# boron-programmer.net
KiCad netlist of a schematic drawn in EAGLE
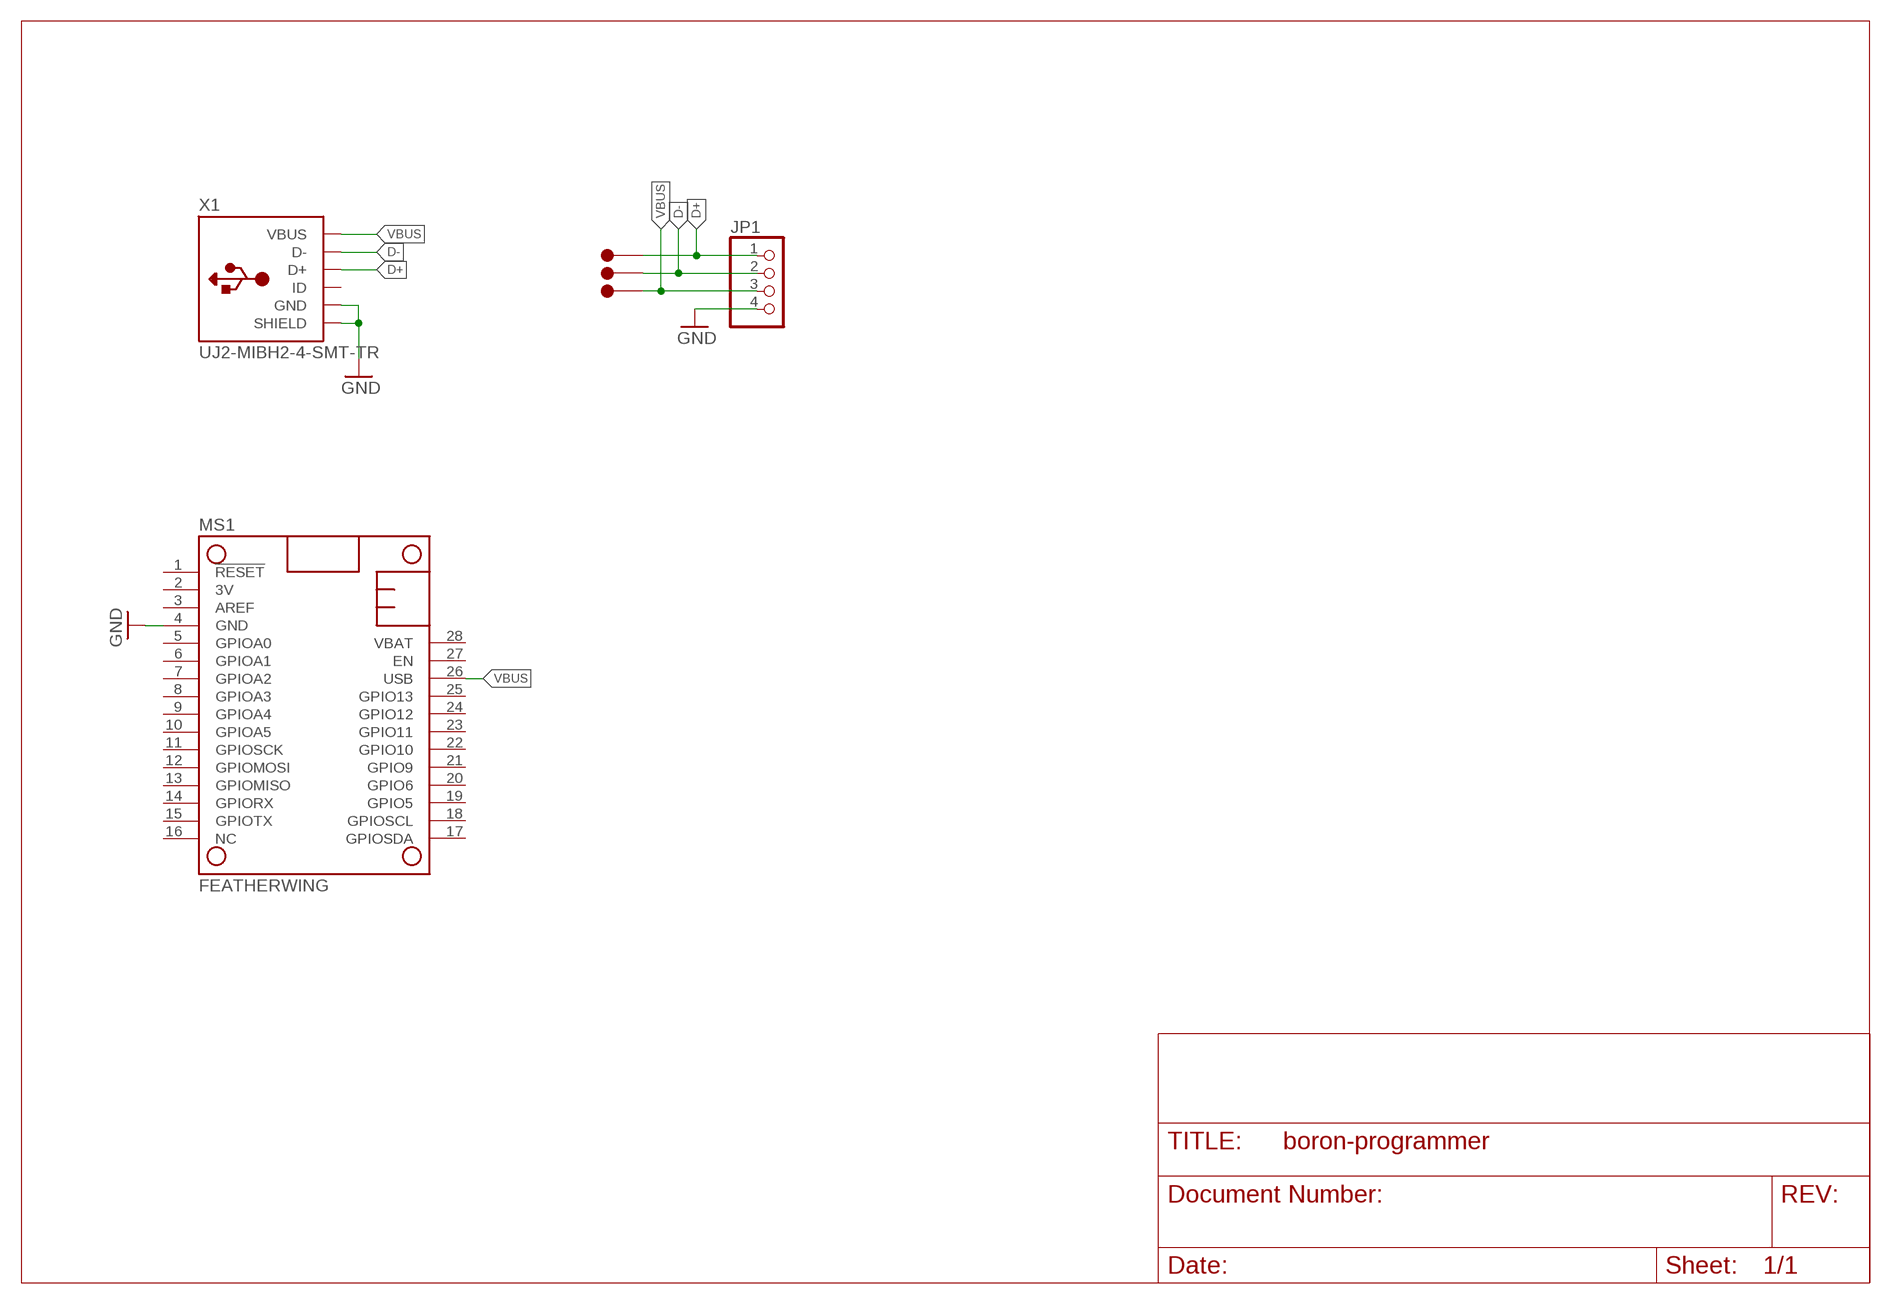
[diagram p0: schematic, sheet 1]

(export (version "E")
  (design (tool "Eeschema 10.0.6"))
  (components
    (comp (ref "C1")
      (value "POGO_PIN_1MM")
      (footprint "eagle-import:POGO_1MM")
      (libsource (lib "eagle-import") (part "POGO_PIN_1MM"))
    )
    (comp (ref "C2")
      (value "POGO_PIN_1MM")
      (footprint "eagle-import:POGO_1MM")
      (libsource (lib "eagle-import") (part "POGO_PIN_1MM"))
    )
    (comp (ref "C4")
      (value "POGO_PIN_1MM")
      (footprint "eagle-import:POGO_1MM")
      (libsource (lib "eagle-import") (part "POGO_PIN_1MM"))
    )
    (comp (ref "JP1")
      (value "PINHD-1X4")
      (footprint "eagle-import:1X04")
      (libsource (lib "eagle-import") (part "PINHD-1X4"))
    )
    (comp (ref "MS1")
      (value "FEATHERWING")
      (footprint "eagle-import:FEATHERWING")
      (libsource (lib "eagle-import") (part "FEATHERWING"))
    )
    (comp (ref "X1")
      (value "UJ2-MIBH2-4-SMT-TR")
      (footprint "eagle-import:MICRO_USB_B")
      (libsource (lib "eagle-import") (part "MICRO_USB_B"))
    )
  )
  (nets
    (net (code "1") (name "/3V") (class "Default")
      (node (ref "MS1") (pin "2") (pinfunction "3V_2") (pintype "power_in"))
    )
    (net (code "2") (name "/VBAT") (class "Default")
      (node (ref "MS1") (pin "28") (pinfunction "VBAT_28") (pintype "power_in"))
    )
    (net (code "3") (name "D+") (class "Default")
      (node (ref "C1") (pin "P$1") (pinfunction "P$1_P$1") (pintype "passive"))
      (node (ref "JP1") (pin "1") (pinfunction "1_1") (pintype "passive"))
      (node (ref "X1") (pin "D+") (pinfunction "D+_D+") (pintype "bidirectional"))
    )
    (net (code "4") (name "D-") (class "Default")
      (node (ref "C2") (pin "P$1") (pinfunction "P$1_P$1") (pintype "passive"))
      (node (ref "JP1") (pin "2") (pinfunction "2_2") (pintype "passive"))
      (node (ref "X1") (pin "D-") (pinfunction "D-_D-") (pintype "bidirectional"))
    )
    (net (code "5") (name "GND") (class "Default")
      (node (ref "JP1") (pin "4") (pinfunction "4_4") (pintype "passive"))
      (node (ref "MS1") (pin "4") (pinfunction "GND_4") (pintype "power_in"))
      (node (ref "X1") (pin "GND") (pinfunction "GND_GND") (pintype "power_in"))
      (node (ref "X1") (pin "SHIELD1") (pinfunction "SHIELD_SHIELD1") (pintype "passive"))
      (node (ref "X1") (pin "SHIELD2") (pinfunction "SHIELD_SHIELD2") (pintype "passive"))
      (node (ref "X1") (pin "SHIELD3") (pinfunction "SHIELD_SHIELD3") (pintype "passive"))
      (node (ref "X1") (pin "SHIELD4") (pinfunction "SHIELD_SHIELD4") (pintype "passive"))
      (node (ref "X1") (pin "SHIELD5") (pinfunction "SHIELD_SHIELD5") (pintype "passive"))
    )
    (net (code "6") (name "VBUS") (class "Default")
      (node (ref "C4") (pin "P$1") (pinfunction "P$1_P$1") (pintype "passive"))
      (node (ref "JP1") (pin "3") (pinfunction "3_3") (pintype "passive"))
      (node (ref "MS1") (pin "26") (pinfunction "USB_26") (pintype "power_in"))
      (node (ref "X1") (pin "VBUS") (pinfunction "VBUS_VBUS") (pintype "power_in"))
    )
    (net (code "7") (name "unconnected-(MS1-AREF-Pad3)") (class "Default")
      (node (ref "MS1") (pin "3") (pinfunction "AREF_3") (pintype "passive"))
    )
    (net (code "8") (name "unconnected-(MS1-EN-Pad27)") (class "Default")
      (node (ref "MS1") (pin "27") (pinfunction "EN_27") (pintype "passive"))
    )
    (net (code "9") (name "unconnected-(MS1-GPIO5-Pad19)") (class "Default")
      (node (ref "MS1") (pin "19") (pinfunction "GPIO5_19") (pintype "bidirectional"))
    )
    (net (code "10") (name "unconnected-(MS1-GPIO6-Pad20)") (class "Default")
      (node (ref "MS1") (pin "20") (pinfunction "GPIO6_20") (pintype "bidirectional"))
    )
    (net (code "11") (name "unconnected-(MS1-GPIO9-Pad21)") (class "Default")
      (node (ref "MS1") (pin "21") (pinfunction "GPIO9_21") (pintype "bidirectional"))
    )
    (net (code "12") (name "unconnected-(MS1-GPIO10-Pad22)") (class "Default")
      (node (ref "MS1") (pin "22") (pinfunction "GPIO10_22") (pintype "bidirectional"))
    )
    (net (code "13") (name "unconnected-(MS1-GPIO11-Pad23)") (class "Default")
      (node (ref "MS1") (pin "23") (pinfunction "GPIO11_23") (pintype "bidirectional"))
    )
    (net (code "14") (name "unconnected-(MS1-GPIO12-Pad24)") (class "Default")
      (node (ref "MS1") (pin "24") (pinfunction "GPIO12_24") (pintype "bidirectional"))
    )
    (net (code "15") (name "unconnected-(MS1-GPIO13-Pad25)") (class "Default")
      (node (ref "MS1") (pin "25") (pinfunction "GPIO13_25") (pintype "bidirectional"))
    )
    (net (code "16") (name "unconnected-(MS1-GPIOA0-Pad5)") (class "Default")
      (node (ref "MS1") (pin "5") (pinfunction "GPIOA0_5") (pintype "bidirectional"))
    )
    (net (code "17") (name "unconnected-(MS1-GPIOA1-Pad6)") (class "Default")
      (node (ref "MS1") (pin "6") (pinfunction "GPIOA1_6") (pintype "bidirectional"))
    )
    (net (code "18") (name "unconnected-(MS1-GPIOA2-Pad7)") (class "Default")
      (node (ref "MS1") (pin "7") (pinfunction "GPIOA2_7") (pintype "bidirectional"))
    )
    (net (code "19") (name "unconnected-(MS1-GPIOA3-Pad8)") (class "Default")
      (node (ref "MS1") (pin "8") (pinfunction "GPIOA3_8") (pintype "bidirectional"))
    )
    (net (code "20") (name "unconnected-(MS1-GPIOA4-Pad9)") (class "Default")
      (node (ref "MS1") (pin "9") (pinfunction "GPIOA4_9") (pintype "bidirectional"))
    )
    (net (code "21") (name "unconnected-(MS1-GPIOA5-Pad10)") (class "Default")
      (node (ref "MS1") (pin "10") (pinfunction "GPIOA5_10") (pintype "bidirectional"))
    )
    (net (code "22") (name "unconnected-(MS1-GPIOMISO-Pad13)") (class "Default")
      (node (ref "MS1") (pin "13") (pinfunction "GPIOMISO_13") (pintype "bidirectional"))
    )
    (net (code "23") (name "unconnected-(MS1-GPIOMOSI-Pad12)") (class "Default")
      (node (ref "MS1") (pin "12") (pinfunction "GPIOMOSI_12") (pintype "bidirectional"))
    )
    (net (code "24") (name "unconnected-(MS1-GPIORX-Pad14)") (class "Default")
      (node (ref "MS1") (pin "14") (pinfunction "GPIORX_14") (pintype "bidirectional"))
    )
    (net (code "25") (name "unconnected-(MS1-GPIOSCK-Pad11)") (class "Default")
      (node (ref "MS1") (pin "11") (pinfunction "GPIOSCK_11") (pintype "bidirectional"))
    )
    (net (code "26") (name "unconnected-(MS1-GPIOSCL-Pad18)") (class "Default")
      (node (ref "MS1") (pin "18") (pinfunction "GPIOSCL_18") (pintype "bidirectional"))
    )
    (net (code "27") (name "unconnected-(MS1-GPIOSDA-Pad17)") (class "Default")
      (node (ref "MS1") (pin "17") (pinfunction "GPIOSDA_17") (pintype "bidirectional"))
    )
    (net (code "28") (name "unconnected-(MS1-GPIOTX-Pad15)") (class "Default")
      (node (ref "MS1") (pin "15") (pinfunction "GPIOTX_15") (pintype "bidirectional"))
    )
    (net (code "29") (name "unconnected-(MS1-NC-Pad16)") (class "Default")
      (node (ref "MS1") (pin "16") (pinfunction "NC_16") (pintype "passive"))
    )
    (net (code "30") (name "unconnected-(MS1-~{RESET}-Pad1)") (class "Default")
      (node (ref "MS1") (pin "1") (pinfunction "~{RESET}_1") (pintype "input"))
    )
    (net (code "31") (name "unconnected-(X1-PadID)") (class "Default")
      (node (ref "X1") (pin "ID") (pinfunction "ID_ID") (pintype "bidirectional"))
    )
  )
)
